# ALL_COMPLETED_COMPONENTS.net
KiCad netlist of a schematic drawn in Altium Designer
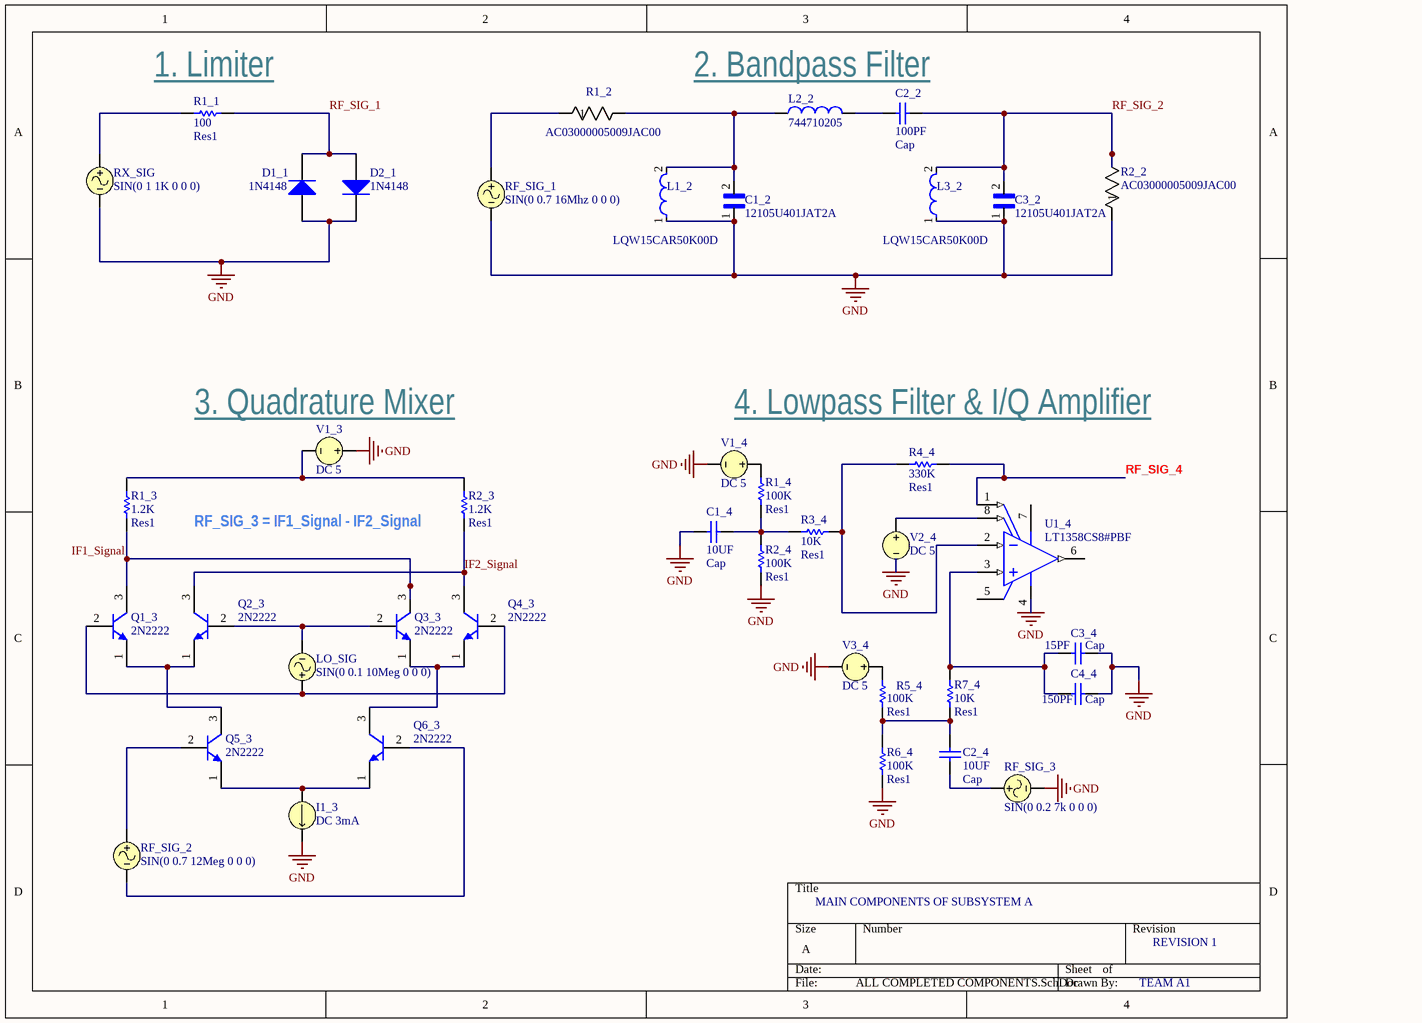
[diagram p0: ALL COMPLETED COMPONENTS.SchDoc]

(export (version "E")
  (design (tool "Eeschema 10.0.6"))
  (components
    (comp (ref "C1_2")
      (value "12105U401JAT2A")
      (footprint "CAPC3224X140N")
      (description "CAP CER 400PF 50V 5% NP0 1210")
      (libsource (lib "12105U401JAT2A") (part "12105U401JAT2A"))
    )
    (comp (ref "C1_4")
      (value "Cap")
      (footprint "RADIAL-0.1")
      (description "Capacitor")
      (fields
        (field (name "ALTIUM_VALUE") "10UF")
        (field (name "MANUFACTURER PART NUMBER") "ESK106M063AC3FA")
        (field (name "PUBLISHER") "Altium Limited")
      )
      (libsource (lib "ECE295-Capacitors-TH") (part "CAP ALUM 10UF 20% 63V RADIAL"))
    )
    (comp (ref "C2_2")
      (value "Cap")
      (footprint "RADIAL-0.1")
      (description "Capacitor")
      (fields
        (field (name "ALTIUM_VALUE") "100PF")
        (field (name "MANUFACTURER PART NUMBER") "K101K15C0GF53L2")
        (field (name "PUBLISHER") "Altium Limited")
      )
      (libsource (lib "ECE295-Capacitors-TH") (part "CAP CER 100PF 50V C0G/NP0 RADIAL"))
    )
    (comp (ref "C2_4")
      (value "Cap")
      (footprint "RADIAL-0.1")
      (description "Capacitor")
      (fields
        (field (name "ALTIUM_VALUE") "10UF")
        (field (name "MANUFACTURER PART NUMBER") "ESK106M063AC3FA")
        (field (name "PUBLISHER") "Altium Limited")
      )
      (libsource (lib "ECE295-Capacitors-TH") (part "CAP ALUM 10UF 20% 63V RADIAL"))
    )
    (comp (ref "C3_2")
      (value "12105U401JAT2A")
      (footprint "CAPC3224X140N")
      (description "CAP CER 400PF 50V 5% NP0 1210")
      (libsource (lib "12105U401JAT2A") (part "12105U401JAT2A"))
    )
    (comp (ref "C3_4")
      (value "Cap")
      (footprint "RADIAL-0.1")
      (description "Capacitor")
      (fields
        (field (name "ALTIUM_VALUE") "15PF")
        (field (name "MANUFACTURER PART NUMBER") "K150J15C0GF5TL2")
        (field (name "PUBLISHER") "Altium Limited")
      )
      (libsource (lib "ECE295-Capacitors-TH") (part "CAP CER 15PF 50V C0G/NP0 RADIAL"))
    )
    (comp (ref "C4_4")
      (value "Cap")
      (footprint "RADIAL-0.1")
      (description "Capacitor")
      (fields
        (field (name "ALTIUM_VALUE") "150PF")
        (field (name "MANUFACTURER PART NUMBER") "K151J15C0GF53L2")
        (field (name "PUBLISHER") "Altium Limited")
      )
      (libsource (lib "ECE295-Capacitors-TH") (part "CAP CER 150PF 50V C0G/NP0 RADIAL"))
    )
    (comp (ref "D1_1")
      (value "1N4148")
      (footprint "NXP-SOD27-2_V")
      (description "High-speed Diode, 100 V, 450 mA, 2-Pin SOD27, RoHS")
      (fields (field (name "MANUFACTURER") "NXP Semiconductors"))
      (libsource (lib "Altium Content Vault") (part "NXP-A1K2-2"))
    )
    (comp (ref "D2_1")
      (value "1N4148")
      (footprint "NXP-SOD27-2_V")
      (description "High-speed Diode, 100 V, 450 mA, 2-Pin SOD27, RoHS")
      (fields (field (name "MANUFACTURER") "NXP Semiconductors"))
      (libsource (lib "Altium Content Vault") (part "NXP-A1K2-2"))
    )
    (comp (ref "I1_3")
      (value "DC 3mA")
      (description "Current Source")
      (fields (field (name "PUBLISHER") "Altium Limited"))
      (libsource (lib "Simulation Generic Components") (part "ISRC"))
    )
    (comp (ref "L1_2")
      (value "LQW15CAR50K00D")
      (footprint "FP-LQW15CA_00-MFG")
      (description "Wire Wound Ferrite Inductor for General Circuits 500nH ±10% 270mA 0.97Ω 0402 (1005)")
      (fields (field (name "TOLERANCE") "10%"))
      (libsource (lib "Altium Content Vault") (part "725321dda6339637d4d059423bc1c3c"))
    )
    (comp (ref "L2_2")
      (value "744710205")
      (footprint "744710205")
      (description "2 µH Unshielded Drum Core, Wirewound Inductor 5 A 6.5mOhm Radial, Horizontal Cylinder (Open)")
      (fields (field (name "TOLERANCE") "25%"))
      (libsource (lib "Altium Content Vault") (part "Inductor - 1"))
    )
    (comp (ref "L3_2")
      (value "LQW15CAR50K00D")
      (footprint "FP-LQW15CA_00-MFG")
      (description "Wire Wound Ferrite Inductor for General Circuits 500nH ±10% 270mA 0.97Ω 0402 (1005)")
      (fields (field (name "TOLERANCE") "10%"))
      (libsource (lib "Altium Content Vault") (part "725321dda6339637d4d059423bc1c3c"))
    )
    (comp (ref "LO_SIG")
      (value "SIN(0 0.1 10Meg 0 0 0)")
      (description "Sinusoidal Voltage Source")
      (fields (field (name "PUBLISHER") "Altium Limited"))
      (libsource (lib "Simulation Generic Components") (part "VSIN"))
    )
    (comp (ref "Q1_3")
      (value "2N2222")
      (footprint "MLTC-TO-18-3")
      (description "Low Power Bipolar NPN Transistor, 30 V, -65 to 200 degC, 3-Pin TO-18, RoHS, Bulk")
      (fields (field (name "MANUFACTURER") "Multicomp"))
      (libsource (lib "Altium Content Vault") (part "BJT-NPN-EBC-3"))
    )
    (comp (ref "Q2_3")
      (value "2N2222")
      (footprint "MLTC-TO-18-3")
      (description "Low Power Bipolar NPN Transistor, 30 V, -65 to 200 degC, 3-Pin TO-18, RoHS, Bulk")
      (fields (field (name "MANUFACTURER") "Multicomp"))
      (libsource (lib "Altium Content Vault") (part "BJT-NPN-EBC-3"))
    )
    (comp (ref "Q3_3")
      (value "2N2222")
      (footprint "MLTC-TO-18-3")
      (description "Low Power Bipolar NPN Transistor, 30 V, -65 to 200 degC, 3-Pin TO-18, RoHS, Bulk")
      (fields (field (name "MANUFACTURER") "Multicomp"))
      (libsource (lib "Altium Content Vault") (part "BJT-NPN-EBC-3"))
    )
    (comp (ref "Q4_3")
      (value "2N2222")
      (footprint "MLTC-TO-18-3")
      (description "Low Power Bipolar NPN Transistor, 30 V, -65 to 200 degC, 3-Pin TO-18, RoHS, Bulk")
      (fields (field (name "MANUFACTURER") "Multicomp"))
      (libsource (lib "Altium Content Vault") (part "BJT-NPN-EBC-3"))
    )
    (comp (ref "Q5_3")
      (value "2N2222")
      (footprint "MLTC-TO-18-3")
      (description "Low Power Bipolar NPN Transistor, 30 V, -65 to 200 degC, 3-Pin TO-18, RoHS, Bulk")
      (fields (field (name "MANUFACTURER") "Multicomp"))
      (libsource (lib "Altium Content Vault") (part "BJT-NPN-EBC-3"))
    )
    (comp (ref "Q6_3")
      (value "2N2222")
      (footprint "MLTC-TO-18-3")
      (description "Low Power Bipolar NPN Transistor, 30 V, -65 to 200 degC, 3-Pin TO-18, RoHS, Bulk")
      (fields (field (name "MANUFACTURER") "Multicomp"))
      (libsource (lib "Altium Content Vault") (part "BJT-NPN-EBC-3"))
    )
    (comp (ref "R1_1")
      (value "Res1")
      (footprint "AXIAL-0.1-RES")
      (description "Resistor")
      (fields
        (field (name "ALTIUM_VALUE") "100")
        (field (name "MANUFACTURER PART NUMBER") "CFR-25JB-52-100R")
        (field (name "TOLERANCE") "0.05")
        (field (name "PUBLISHER") "Altium Limited")
      )
      (libsource (lib "ECE295-Resistors-TH") (part "RES 100 OHM 5% 1/4W AXIAL"))
    )
    (comp (ref "R1_2")
      (value "AC03000005009JAC00")
      (footprint "RES_AC03_VIS")
      (fields (field (name "TOLERANCE") "5%"))
      (libsource (lib "Altium Content Vault") (part "AC03000005009JAC00"))
    )
    (comp (ref "R1_3")
      (value "Res1")
      (footprint "AXIAL-0.1-RES")
      (description "Resistor")
      (fields
        (field (name "ALTIUM_VALUE") "1.2K")
        (field (name "MANUFACTURER PART NUMBER") "CFR-25JB-52-1K2")
        (field (name "TOLERANCE") "0.05")
        (field (name "PUBLISHER") "Altium Limited")
      )
      (libsource (lib "ECE295-Resistors-TH") (part "RES 1.2K OHM 5% 1/4W AXIAL"))
    )
    (comp (ref "R1_4")
      (value "Res1")
      (footprint "AXIAL-0.1-RES")
      (description "Resistor")
      (fields
        (field (name "ALTIUM_VALUE") "100K")
        (field (name "MANUFACTURER PART NUMBER") "CFR-25JB-52-100K")
        (field (name "TOLERANCE") "0.05")
        (field (name "PUBLISHER") "Altium Limited")
      )
      (libsource (lib "ECE295-Resistors-TH") (part "RES 100K OHM 5% 1/4W AXIAL"))
    )
    (comp (ref "R2_2")
      (value "AC03000005009JAC00")
      (footprint "RES_AC03_VIS")
      (fields (field (name "TOLERANCE") "5%"))
      (libsource (lib "Altium Content Vault") (part "AC03000005009JAC00"))
    )
    (comp (ref "R2_3")
      (value "Res1")
      (footprint "AXIAL-0.1-RES")
      (description "Resistor")
      (fields
        (field (name "ALTIUM_VALUE") "1.2K")
        (field (name "MANUFACTURER PART NUMBER") "CFR-25JB-52-1K2")
        (field (name "TOLERANCE") "0.05")
        (field (name "PUBLISHER") "Altium Limited")
      )
      (libsource (lib "ECE295-Resistors-TH") (part "RES 1.2K OHM 5% 1/4W AXIAL"))
    )
    (comp (ref "R2_4")
      (value "Res1")
      (footprint "AXIAL-0.1-RES")
      (description "Resistor")
      (fields
        (field (name "ALTIUM_VALUE") "100K")
        (field (name "MANUFACTURER PART NUMBER") "CFR-25JB-52-100K")
        (field (name "TOLERANCE") "0.05")
        (field (name "PUBLISHER") "Altium Limited")
      )
      (libsource (lib "ECE295-Resistors-TH") (part "RES 100K OHM 5% 1/4W AXIAL"))
    )
    (comp (ref "R3_4")
      (value "Res1")
      (footprint "AXIAL-0.1-RES")
      (description "Resistor")
      (fields
        (field (name "ALTIUM_VALUE") "10K")
        (field (name "MANUFACTURER PART NUMBER") "CFR-25JB-52-10K")
        (field (name "TOLERANCE") "0.05")
        (field (name "PUBLISHER") "Altium Limited")
      )
      (libsource (lib "ECE295-Resistors-TH") (part "RES 10K OHM 5% 1/4W AXIAL"))
    )
    (comp (ref "R4_4")
      (value "Res1")
      (footprint "AXIAL-0.1-RES")
      (description "Resistor")
      (fields
        (field (name "ALTIUM_VALUE") "330K")
        (field (name "MANUFACTURER PART NUMBER") "CFR-25JB-52-330K")
        (field (name "TOLERANCE") "0.05")
        (field (name "PUBLISHER") "Altium Limited")
      )
      (libsource (lib "ECE295-Resistors-TH") (part "RES 330K OHM 5% 1/4W AXIAL"))
    )
    (comp (ref "R5_4")
      (value "Res1")
      (footprint "AXIAL-0.1-RES")
      (description "Resistor")
      (fields
        (field (name "ALTIUM_VALUE") "100K")
        (field (name "MANUFACTURER PART NUMBER") "CFR-25JB-52-100K")
        (field (name "TOLERANCE") "0.05")
        (field (name "PUBLISHER") "Altium Limited")
      )
      (libsource (lib "ECE295-Resistors-TH") (part "RES 100K OHM 5% 1/4W AXIAL"))
    )
    (comp (ref "R6_4")
      (value "Res1")
      (footprint "AXIAL-0.1-RES")
      (description "Resistor")
      (fields
        (field (name "ALTIUM_VALUE") "100K")
        (field (name "MANUFACTURER PART NUMBER") "CFR-25JB-52-100K")
        (field (name "TOLERANCE") "0.05")
        (field (name "PUBLISHER") "Altium Limited")
      )
      (libsource (lib "ECE295-Resistors-TH") (part "RES 100K OHM 5% 1/4W AXIAL"))
    )
    (comp (ref "R7_4")
      (value "Res1")
      (footprint "AXIAL-0.1-RES")
      (description "Resistor")
      (fields
        (field (name "ALTIUM_VALUE") "10K")
        (field (name "MANUFACTURER PART NUMBER") "CFR-25JB-52-10K")
        (field (name "TOLERANCE") "0.05")
        (field (name "PUBLISHER") "Altium Limited")
      )
      (libsource (lib "ECE295-Resistors-TH") (part "RES 10K OHM 5% 1/4W AXIAL"))
    )
    (comp (ref "RF_SIG_1")
      (value "SIN(0 0.7 16Mhz 0 0 0)")
      (description "Sinusoidal Voltage Source")
      (fields (field (name "PUBLISHER") "Altium Limited"))
      (libsource (lib "Simulation Generic Components") (part "VSIN"))
    )
    (comp (ref "RF_SIG_2")
      (value "SIN(0 0.7 12Meg 0 0 0)")
      (description "Sinusoidal Voltage Source")
      (fields (field (name "PUBLISHER") "Altium Limited"))
      (libsource (lib "Simulation Generic Components") (part "VSIN"))
    )
    (comp (ref "RF_SIG_3")
      (value "SIN(0 0.2 7k 0 0 0)")
      (description "Sinusoidal Voltage Source")
      (fields (field (name "PUBLISHER") "Altium Limited"))
      (libsource (lib "Simulation Generic Components") (part "VSIN"))
    )
    (comp (ref "RX_SIG")
      (value "SIN(0 1 1K 0 0 0)")
      (description "Sinusoidal Voltage Source")
      (fields (field (name "PUBLISHER") "Altium Limited"))
      (libsource (lib "Simulation Generic Components") (part "VSIN"))
    )
    (comp (ref "U1_4")
      (value "LT1358CS8#PBF")
      (footprint "LT-S8-8_M")
      (fields
        (field (name "MANUFACTURER") "Linear Technology")
        (field (name "LINEAR TECHNOLOGY PART NUMBER") "LT1358")
      )
      (libsource (lib "Altium Content Vault") (part "LT-LT135X-LT136X-8"))
    )
    (comp (ref "V1_3")
      (value "DC 5")
      (description "Voltage Source")
      (fields (field (name "PUBLISHER") "Altium Limited"))
      (libsource (lib "Simulation Generic Components") (part "VSRC"))
    )
    (comp (ref "V1_4")
      (value "DC 5")
      (description "Voltage Source")
      (fields (field (name "PUBLISHER") "Altium Limited"))
      (libsource (lib "Simulation Generic Components") (part "VSRC"))
    )
    (comp (ref "V2_4")
      (value "DC 5")
      (description "Voltage Source")
      (fields (field (name "PUBLISHER") "Altium Limited"))
      (libsource (lib "Simulation Generic Components") (part "VSRC"))
    )
    (comp (ref "V3_4")
      (value "DC 5")
      (description "Voltage Source")
      (fields (field (name "PUBLISHER") "Altium Limited"))
      (libsource (lib "Simulation Generic Components") (part "VSRC"))
    )
  )
  (nets
    (net (code "1") (name "/IF1_Signal") (class "Default")
      (node (ref "Q1_3") (pin "3") (pinfunction "C_3") (pintype "passive"))
      (node (ref "Q3_3") (pin "3") (pinfunction "C_3") (pintype "passive"))
      (node (ref "R1_3") (pin "1") (pinfunction "1_1") (pintype "passive"))
    )
    (net (code "2") (name "/IF2_Signal") (class "Default")
      (node (ref "Q2_3") (pin "3") (pinfunction "C_3") (pintype "passive"))
      (node (ref "Q4_3") (pin "3") (pinfunction "C_3") (pintype "passive"))
      (node (ref "R2_3") (pin "1") (pinfunction "1_1") (pintype "passive"))
    )
    (net (code "3") (name "/RF_SIG_1") (class "Default")
      (node (ref "D1_1") (pin "2") (pinfunction "K_2") (pintype "passive"))
      (node (ref "D2_1") (pin "1") (pinfunction "A_1") (pintype "passive"))
      (node (ref "R1_1") (pin "2") (pinfunction "2_2") (pintype "passive"))
    )
    (net (code "4") (name "/RF_SIG_2") (class "Default")
      (node (ref "C2_2") (pin "2") (pinfunction "2_2") (pintype "passive"))
      (node (ref "C3_2") (pin "2") (pinfunction "2_2") (pintype "passive"))
      (node (ref "L3_2") (pin "2") (pinfunction "2_2") (pintype "passive"))
      (node (ref "R2_2") (pin "2") (pinfunction "2_2") (pintype "passive"))
    )
    (net (code "5") (name "/RF_SIG_4") (class "Default")
      (node (ref "R4_4") (pin "2") (pinfunction "2_2") (pintype "passive"))
      (node (ref "U1_4") (pin "1") (pinfunction "NULL_1") (pintype "input"))
    )
    (net (code "6") (name "GND") (class "Default")
      (node (ref "C1_2") (pin "1") (pinfunction "1_1") (pintype "passive"))
      (node (ref "C1_4") (pin "1") (pinfunction "1_1") (pintype "passive"))
      (node (ref "C3_2") (pin "1") (pinfunction "1_1") (pintype "passive"))
      (node (ref "C3_4") (pin "2") (pinfunction "2_2") (pintype "passive"))
      (node (ref "C4_4") (pin "1") (pinfunction "1_1") (pintype "passive"))
      (node (ref "D1_1") (pin "1") (pinfunction "A_1") (pintype "passive"))
      (node (ref "D2_1") (pin "2") (pinfunction "K_2") (pintype "passive"))
      (node (ref "I1_3") (pin "2") (pinfunction "2_2") (pintype "passive"))
      (node (ref "L1_2") (pin "1") (pinfunction "1_1") (pintype "passive"))
      (node (ref "L3_2") (pin "1") (pinfunction "1_1") (pintype "passive"))
      (node (ref "R2_2") (pin "1") (pinfunction "1_1") (pintype "passive"))
      (node (ref "R2_4") (pin "1") (pinfunction "1_1") (pintype "passive"))
      (node (ref "R6_4") (pin "1") (pinfunction "1_1") (pintype "passive"))
      (node (ref "RF_SIG_1") (pin "2") (pinfunction "2_2") (pintype "passive"))
      (node (ref "RF_SIG_3") (pin "2") (pinfunction "2_2") (pintype "passive"))
      (node (ref "RX_SIG") (pin "2") (pinfunction "2_2") (pintype "passive"))
      (node (ref "U1_4") (pin "4") (pinfunction "V-_4") (pintype "power_in"))
      (node (ref "V1_3") (pin "1") (pinfunction "1_1") (pintype "passive"))
      (node (ref "V1_4") (pin "2") (pinfunction "2_2") (pintype "passive"))
      (node (ref "V2_4") (pin "2") (pinfunction "2_2") (pintype "passive"))
      (node (ref "V3_4") (pin "2") (pinfunction "2_2") (pintype "passive"))
    )
    (net (code "7") (name "Net-(C1_2-Pad2)") (class "Default")
      (node (ref "C1_2") (pin "2") (pinfunction "2_2") (pintype "passive"))
      (node (ref "L1_2") (pin "2") (pinfunction "2_2") (pintype "passive"))
      (node (ref "L2_2") (pin "1") (pinfunction "1_1") (pintype "passive"))
      (node (ref "R1_2") (pin "2") (pinfunction "2_2") (pintype "passive"))
    )
    (net (code "8") (name "Net-(C1_4-Pad2)") (class "Default")
      (node (ref "C1_4") (pin "2") (pinfunction "2_2") (pintype "passive"))
      (node (ref "R1_4") (pin "1") (pinfunction "1_1") (pintype "passive"))
      (node (ref "R2_4") (pin "2") (pinfunction "2_2") (pintype "passive"))
      (node (ref "R3_4") (pin "1") (pinfunction "1_1") (pintype "passive"))
    )
    (net (code "9") (name "Net-(C2_2-Pad1)") (class "Default")
      (node (ref "C2_2") (pin "1") (pinfunction "1_1") (pintype "passive"))
      (node (ref "L2_2") (pin "2") (pinfunction "2_2") (pintype "passive"))
    )
    (net (code "10") (name "Net-(C2_4-Pad1)") (class "Default")
      (node (ref "C2_4") (pin "1") (pinfunction "1_1") (pintype "passive"))
      (node (ref "RF_SIG_3") (pin "1") (pinfunction "1_1") (pintype "passive"))
    )
    (net (code "11") (name "Net-(C2_4-Pad2)") (class "Default")
      (node (ref "C2_4") (pin "2") (pinfunction "2_2") (pintype "passive"))
      (node (ref "R5_4") (pin "1") (pinfunction "1_1") (pintype "passive"))
      (node (ref "R6_4") (pin "2") (pinfunction "2_2") (pintype "passive"))
      (node (ref "R7_4") (pin "1") (pinfunction "1_1") (pintype "passive"))
    )
    (net (code "12") (name "Net-(Q1_3-B)") (class "Default")
      (node (ref "LO_SIG") (pin "1") (pinfunction "1_1") (pintype "passive"))
      (node (ref "Q1_3") (pin "2") (pinfunction "B_2") (pintype "passive"))
      (node (ref "Q4_3") (pin "2") (pinfunction "B_2") (pintype "passive"))
    )
    (net (code "13") (name "Net-(Q1_3-E)") (class "Default")
      (node (ref "Q1_3") (pin "1") (pinfunction "E_1") (pintype "passive"))
      (node (ref "Q2_3") (pin "1") (pinfunction "E_1") (pintype "passive"))
      (node (ref "Q5_3") (pin "3") (pinfunction "C_3") (pintype "passive"))
    )
    (net (code "14") (name "Net-(Q2_3-B)") (class "Default")
      (node (ref "LO_SIG") (pin "2") (pinfunction "2_2") (pintype "passive"))
      (node (ref "Q2_3") (pin "2") (pinfunction "B_2") (pintype "passive"))
      (node (ref "Q3_3") (pin "2") (pinfunction "B_2") (pintype "passive"))
    )
    (net (code "15") (name "Net-(Q3_3-E)") (class "Default")
      (node (ref "Q3_3") (pin "1") (pinfunction "E_1") (pintype "passive"))
      (node (ref "Q4_3") (pin "1") (pinfunction "E_1") (pintype "passive"))
      (node (ref "Q6_3") (pin "3") (pinfunction "C_3") (pintype "passive"))
    )
    (net (code "16") (name "Net-(Q5_3-B)") (class "Default")
      (node (ref "Q5_3") (pin "2") (pinfunction "B_2") (pintype "passive"))
      (node (ref "RF_SIG_2") (pin "1") (pinfunction "1_1") (pintype "passive"))
    )
    (net (code "17") (name "Net-(Q5_3-E)") (class "Default")
      (node (ref "I1_3") (pin "1") (pinfunction "1_1") (pintype "passive"))
      (node (ref "Q5_3") (pin "1") (pinfunction "E_1") (pintype "passive"))
      (node (ref "Q6_3") (pin "1") (pinfunction "E_1") (pintype "passive"))
    )
    (net (code "18") (name "Net-(Q6_3-B)") (class "Default")
      (node (ref "Q6_3") (pin "2") (pinfunction "B_2") (pintype "passive"))
      (node (ref "RF_SIG_2") (pin "2") (pinfunction "2_2") (pintype "passive"))
    )
    (net (code "19") (name "Net-(R1_1-Pad1)") (class "Default")
      (node (ref "R1_1") (pin "1") (pinfunction "1_1") (pintype "passive"))
      (node (ref "RX_SIG") (pin "1") (pinfunction "1_1") (pintype "passive"))
    )
    (net (code "20") (name "Net-(R1_2-Pad1)") (class "Default")
      (node (ref "R1_2") (pin "1") (pinfunction "1_1") (pintype "passive"))
      (node (ref "RF_SIG_1") (pin "1") (pinfunction "1_1") (pintype "passive"))
    )
    (net (code "21") (name "Net-(R1_3-Pad2)") (class "Default")
      (node (ref "R1_3") (pin "2") (pinfunction "2_2") (pintype "passive"))
      (node (ref "R2_3") (pin "2") (pinfunction "2_2") (pintype "passive"))
      (node (ref "V1_3") (pin "2") (pinfunction "2_2") (pintype "passive"))
    )
    (net (code "22") (name "Net-(R1_4-Pad2)") (class "Default")
      (node (ref "R1_4") (pin "2") (pinfunction "2_2") (pintype "passive"))
      (node (ref "V1_4") (pin "1") (pinfunction "1_1") (pintype "passive"))
    )
    (net (code "23") (name "Net-(R5_4-Pad2)") (class "Default")
      (node (ref "R5_4") (pin "2") (pinfunction "2_2") (pintype "passive"))
      (node (ref "V3_4") (pin "1") (pinfunction "1_1") (pintype "passive"))
    )
    (net (code "24") (name "Net-(U1_4-+IN)") (class "Default")
      (node (ref "C3_4") (pin "1") (pinfunction "1_1") (pintype "passive"))
      (node (ref "C4_4") (pin "2") (pinfunction "2_2") (pintype "passive"))
      (node (ref "R7_4") (pin "2") (pinfunction "2_2") (pintype "passive"))
      (node (ref "U1_4") (pin "3") (pinfunction "+IN_3") (pintype "input"))
    )
    (net (code "25") (name "Net-(U1_4--IN)") (class "Default")
      (node (ref "R3_4") (pin "2") (pinfunction "2_2") (pintype "passive"))
      (node (ref "R4_4") (pin "1") (pinfunction "1_1") (pintype "passive"))
      (node (ref "U1_4") (pin "2") (pinfunction "-IN_2") (pintype "input"))
    )
    (net (code "26") (name "Net-(U1_4-NULL-Pad8)") (class "Default")
      (node (ref "U1_4") (pin "8") (pinfunction "NULL_8") (pintype "input"))
      (node (ref "V2_4") (pin "1") (pinfunction "1_1") (pintype "passive"))
    )
    (net (code "27") (name "unconnected-(U1_4-NC-Pad5)") (class "Default")
      (node (ref "U1_4") (pin "5") (pinfunction "NC_5") (pintype "passive"))
    )
    (net (code "28") (name "unconnected-(U1_4-V+-Pad7)") (class "Default")
      (node (ref "U1_4") (pin "7") (pinfunction "V+_7") (pintype "power_in"))
    )
    (net (code "29") (name "unconnected-(U1_4-VOUT-Pad6)") (class "Default")
      (node (ref "U1_4") (pin "6") (pinfunction "VOUT_6") (pintype "output"))
    )
  )
)
